# 1541-3d.net
KiCad netlist of a schematic drawn in EAGLE
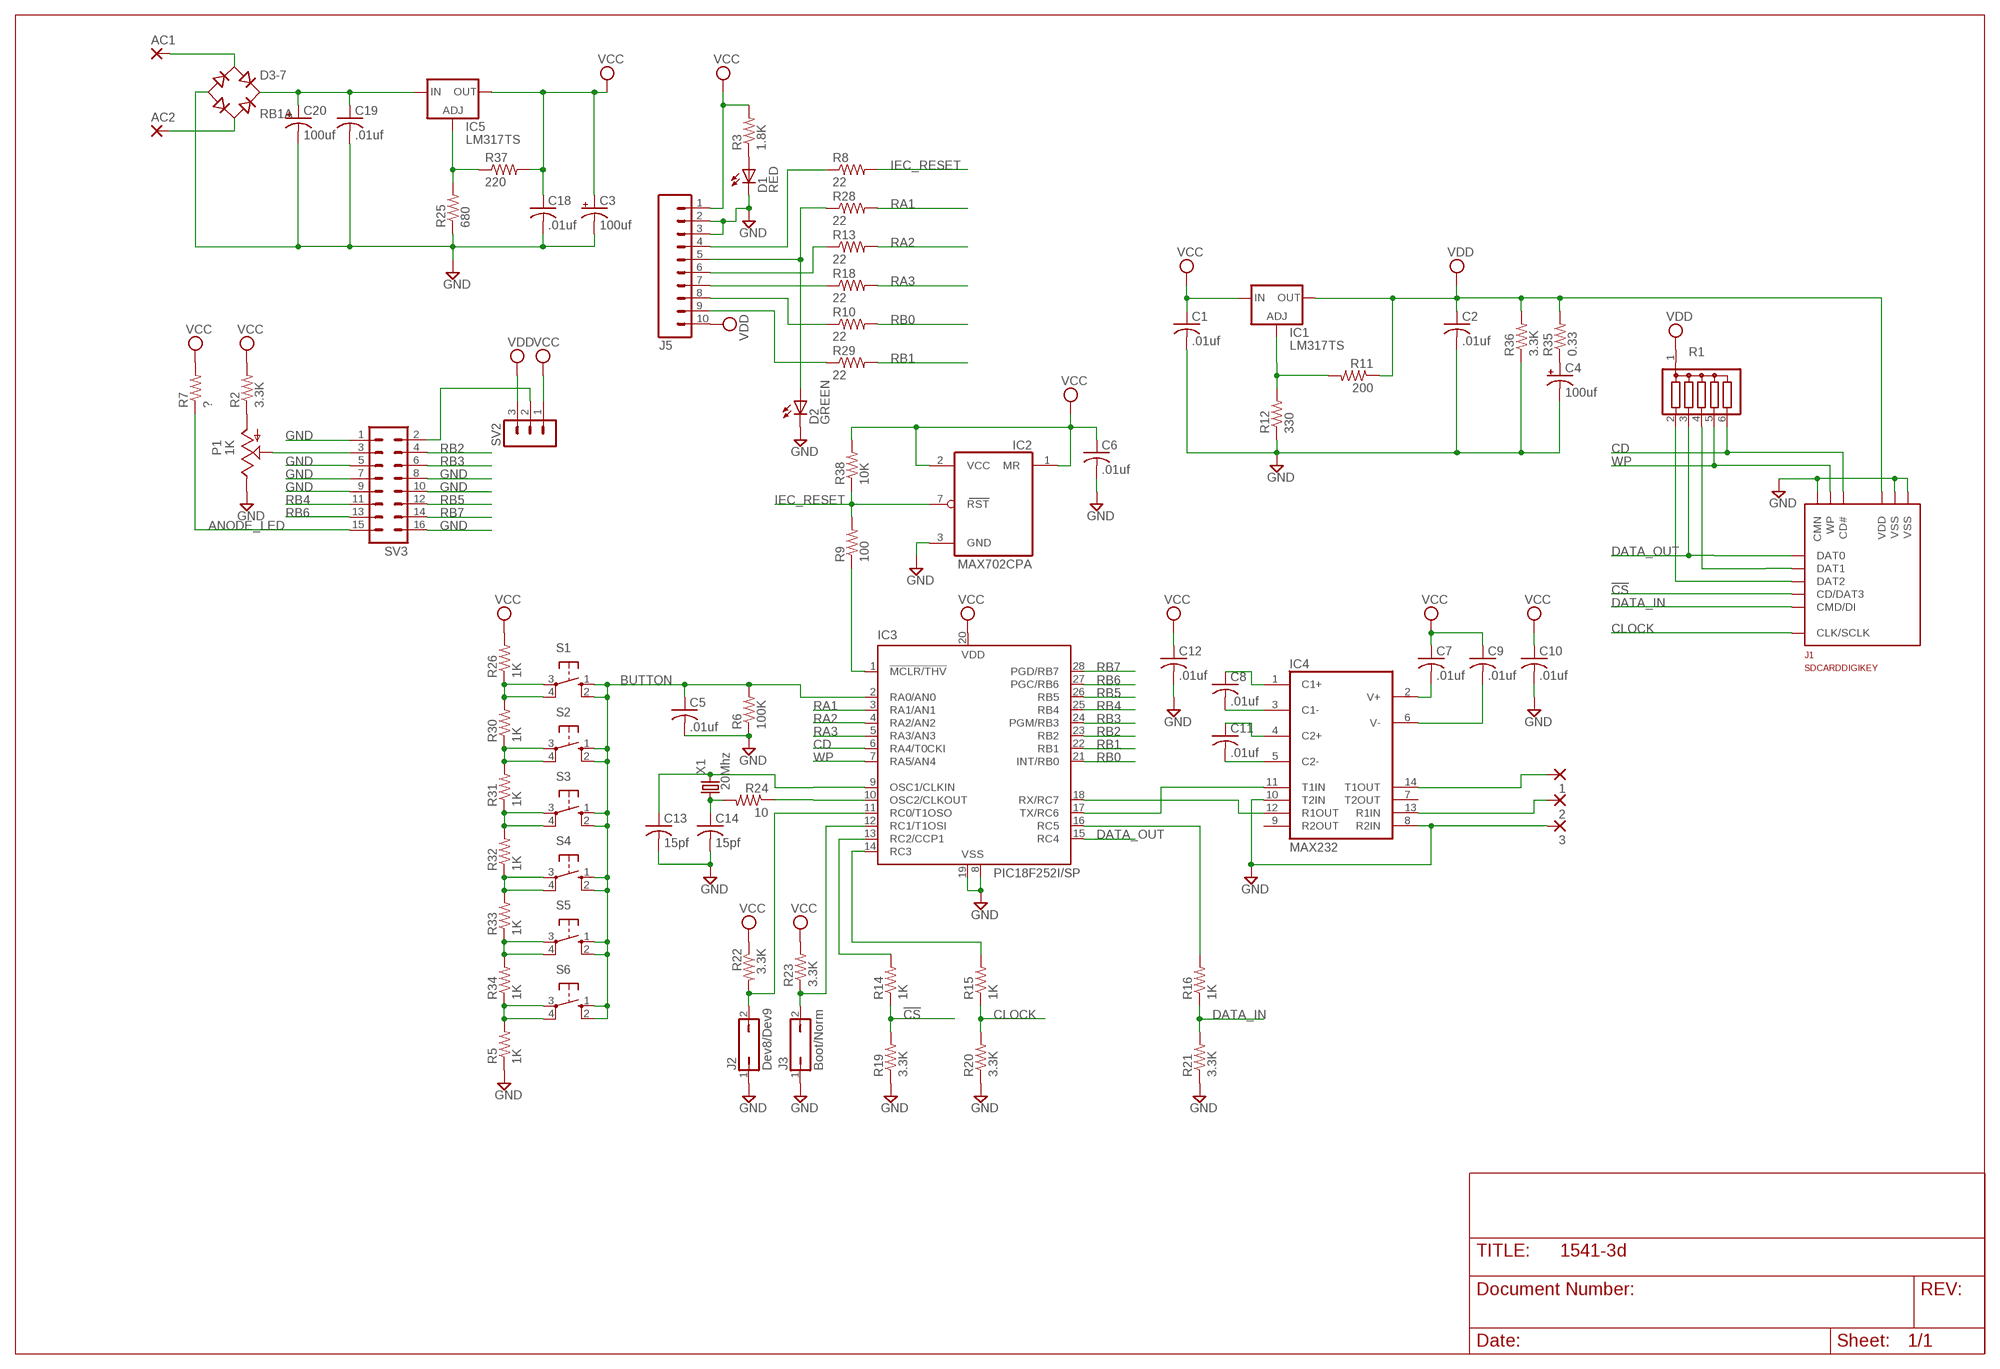
[diagram p0: schematic, sheet 1]

(export (version "E")
  (design (tool "Eeschema 10.0.6"))
  (components
    (comp (ref "1")
      (value "2,15/1,0")
      (footprint "eagle-import:2,15_1,0")
      (libsource (lib "eagle-import") (part "2,15/1,0"))
    )
    (comp (ref "2")
      (value "2,15/1,0")
      (footprint "eagle-import:2,15_1,0")
      (libsource (lib "eagle-import") (part "2,15/1,0"))
    )
    (comp (ref "3")
      (value "2,15/1,0")
      (footprint "eagle-import:2,15_1,0")
      (libsource (lib "eagle-import") (part "2,15/1,0"))
    )
    (comp (ref "AC1")
      (value "2,15/1,0")
      (footprint "eagle-import:2,15_1,0")
      (libsource (lib "eagle-import") (part "2,15/1,0"))
    )
    (comp (ref "AC2")
      (value "2,15/1,0")
      (footprint "eagle-import:2,15_1,0")
      (libsource (lib "eagle-import") (part "2,15/1,0"))
    )
    (comp (ref "C1")
      (value ".01uf")
      (footprint "eagle-import:C025-024X044")
      (libsource (lib "eagle-import") (part "C-US025-024X044"))
    )
    (comp (ref "C2")
      (value ".01uf")
      (footprint "eagle-import:C025-024X044")
      (libsource (lib "eagle-import") (part "C-US025-024X044"))
    )
    (comp (ref "C3")
      (value "100uf")
      (footprint "eagle-import:E2-5")
      (libsource (lib "eagle-import") (part "CPOL-USE2-5"))
    )
    (comp (ref "C4")
      (value "100uf")
      (footprint "eagle-import:E2-5")
      (libsource (lib "eagle-import") (part "CPOL-USE2-5"))
    )
    (comp (ref "C5")
      (value ".01uf")
      (footprint "eagle-import:C025-024X044")
      (libsource (lib "eagle-import") (part "C-US025-024X044"))
    )
    (comp (ref "C6")
      (value ".01uf")
      (footprint "eagle-import:C025-024X044")
      (libsource (lib "eagle-import") (part "C-US025-024X044"))
    )
    (comp (ref "C7")
      (value ".01uf")
      (footprint "eagle-import:C025-024X044")
      (libsource (lib "eagle-import") (part "C-US025-024X044"))
    )
    (comp (ref "C8")
      (value ".01uf")
      (footprint "eagle-import:C025-024X044")
      (libsource (lib "eagle-import") (part "C-US025-024X044"))
    )
    (comp (ref "C9")
      (value ".01uf")
      (footprint "eagle-import:C025-024X044")
      (libsource (lib "eagle-import") (part "C-US025-024X044"))
    )
    (comp (ref "C10")
      (value ".01uf")
      (footprint "eagle-import:C025-024X044")
      (libsource (lib "eagle-import") (part "C-US025-024X044"))
    )
    (comp (ref "C11")
      (value ".01uf")
      (footprint "eagle-import:C025-024X044")
      (libsource (lib "eagle-import") (part "C-US025-024X044"))
    )
    (comp (ref "C12")
      (value ".01uf")
      (footprint "eagle-import:C025-024X044")
      (libsource (lib "eagle-import") (part "C-US025-024X044"))
    )
    (comp (ref "C13")
      (value "15pf")
      (footprint "eagle-import:C025-024X044")
      (libsource (lib "eagle-import") (part "C-US025-024X044"))
    )
    (comp (ref "C14")
      (value "15pf")
      (footprint "eagle-import:C025-024X044")
      (libsource (lib "eagle-import") (part "C-US025-024X044"))
    )
    (comp (ref "C18")
      (value ".01uf")
      (footprint "eagle-import:C025-024X044")
      (libsource (lib "eagle-import") (part "C-US025-024X044"))
    )
    (comp (ref "C19")
      (value ".01uf")
      (footprint "eagle-import:C025-024X044")
      (libsource (lib "eagle-import") (part "C-US025-024X044"))
    )
    (comp (ref "C20")
      (value "100uf")
      (footprint "eagle-import:E2-5")
      (libsource (lib "eagle-import") (part "CPOL-USE2-5"))
    )
    (comp (ref "D1")
      (value "RED")
      (footprint "eagle-import:LED3MM")
      (libsource (lib "eagle-import") (part "LED3MM"))
    )
    (comp (ref "D2")
      (value "GREEN")
      (footprint "eagle-import:LED3MM")
      (libsource (lib "eagle-import") (part "LED3MM"))
    )
    (comp (ref "D3-7")
      (value "RB1A")
      (footprint "eagle-import:RB1A")
      (libsource (lib "eagle-import") (part "RB1A"))
    )
    (comp (ref "IC1")
      (value "LM317TS")
      (footprint "eagle-import:317TS")
      (libsource (lib "eagle-import") (part "LM317TS"))
    )
    (comp (ref "IC2")
      (value "MAX702CPA")
      (footprint "eagle-import:DIL08")
      (fields (field (name "MF") "MAXIM") (field (name "MPN") "MAX702CPA+"))
      (libsource (lib "eagle-import") (part "MAX702CPA"))
    )
    (comp (ref "IC3")
      (value "PIC18F252I/SP")
      (footprint "eagle-import:DIL28-3")
      (fields (field (name "MF") "MICROCHIP") (field (name "MPN") "PIC16F870-I/SP"))
      (libsource (lib "eagle-import") (part "PIC16870PF"))
    )
    (comp (ref "IC4")
      (value "MAX232")
      (footprint "eagle-import:DIL16")
      (fields (field (name "MF") "MAXIM") (field (name "MPN") "MAX232ACPE+"))
      (libsource (lib "eagle-import") (part "MAX232"))
    )
    (comp (ref "IC5")
      (value "LM317TS")
      (footprint "eagle-import:317TS")
      (libsource (lib "eagle-import") (part "LM317TS"))
    )
    (comp (ref "J1")
      (value "SDCARDDIGIKEY")
      (footprint "eagle-import:WM24032")
      (libsource (lib "eagle-import") (part "SDCARDDIGIKEY"))
    )
    (comp (ref "J2")
      (value "Dev8/Dev9")
      (footprint "eagle-import:JP1")
      (libsource (lib "eagle-import") (part "JP1Q"))
    )
    (comp (ref "J3")
      (value "Boot/Norm")
      (footprint "eagle-import:JP1")
      (libsource (lib "eagle-import") (part "JP1Q"))
    )
    (comp (ref "J5")
      (value "M10")
      (footprint "eagle-import:10P")
      (libsource (lib "eagle-import") (part "M10"))
    )
    (comp (ref "P1")
      (value "1K")
      (footprint "eagle-import:LI10")
      (libsource (lib "eagle-import") (part "TRIM_US-LI10"))
    )
    (comp (ref "R1")
      (value "G05R")
      (footprint "eagle-import:SIL6")
      (libsource (lib "eagle-import") (part "G05R"))
    )
    (comp (ref "R2")
      (value "3.3K")
      (footprint "eagle-import:0207_2V")
      (libsource (lib "eagle-import") (part "R-US_0207/2V"))
    )
    (comp (ref "R3")
      (value "1.8K")
      (footprint "eagle-import:0207_2V")
      (libsource (lib "eagle-import") (part "R-US_0207/2V"))
    )
    (comp (ref "R5")
      (value "1K")
      (footprint "eagle-import:0207_2V")
      (libsource (lib "eagle-import") (part "R-US_0207/2V"))
    )
    (comp (ref "R6")
      (value "100K")
      (footprint "eagle-import:0207_2V")
      (libsource (lib "eagle-import") (part "R-US_0207/2V"))
    )
    (comp (ref "R7")
      (value "?")
      (footprint "eagle-import:0207_2V")
      (libsource (lib "eagle-import") (part "R-US_0207/2V"))
    )
    (comp (ref "R8")
      (value "22")
      (footprint "eagle-import:0207_2V")
      (libsource (lib "eagle-import") (part "R-US_0207/2V"))
    )
    (comp (ref "R9")
      (value "100")
      (footprint "eagle-import:0207_2V")
      (libsource (lib "eagle-import") (part "R-US_0207/2V"))
    )
    (comp (ref "R10")
      (value "22")
      (footprint "eagle-import:0207_2V")
      (libsource (lib "eagle-import") (part "R-US_0207/2V"))
    )
    (comp (ref "R11")
      (value "200")
      (footprint "eagle-import:0207_2V")
      (libsource (lib "eagle-import") (part "R-US_0207/2V"))
    )
    (comp (ref "R12")
      (value "330")
      (footprint "eagle-import:0207_2V")
      (libsource (lib "eagle-import") (part "R-US_0207/2V"))
    )
    (comp (ref "R13")
      (value "22")
      (footprint "eagle-import:0207_2V")
      (libsource (lib "eagle-import") (part "R-US_0207/2V"))
    )
    (comp (ref "R14")
      (value "1K")
      (footprint "eagle-import:0207_2V")
      (libsource (lib "eagle-import") (part "R-US_0207/2V"))
    )
    (comp (ref "R15")
      (value "1K")
      (footprint "eagle-import:0207_2V")
      (libsource (lib "eagle-import") (part "R-US_0207/2V"))
    )
    (comp (ref "R16")
      (value "1K")
      (footprint "eagle-import:0207_2V")
      (libsource (lib "eagle-import") (part "R-US_0207/2V"))
    )
    (comp (ref "R18")
      (value "22")
      (footprint "eagle-import:0207_2V")
      (libsource (lib "eagle-import") (part "R-US_0207/2V"))
    )
    (comp (ref "R19")
      (value "3.3K")
      (footprint "eagle-import:0207_2V")
      (libsource (lib "eagle-import") (part "R-US_0207/2V"))
    )
    (comp (ref "R20")
      (value "3.3K")
      (footprint "eagle-import:0207_2V")
      (libsource (lib "eagle-import") (part "R-US_0207/2V"))
    )
    (comp (ref "R21")
      (value "3.3K")
      (footprint "eagle-import:0207_2V")
      (libsource (lib "eagle-import") (part "R-US_0207/2V"))
    )
    (comp (ref "R22")
      (value "3.3K")
      (footprint "eagle-import:0207_2V")
      (libsource (lib "eagle-import") (part "R-US_0207/2V"))
    )
    (comp (ref "R23")
      (value "3.3K")
      (footprint "eagle-import:0207_2V")
      (libsource (lib "eagle-import") (part "R-US_0207/2V"))
    )
    (comp (ref "R24")
      (value "10")
      (footprint "eagle-import:0207_2V")
      (libsource (lib "eagle-import") (part "R-US_0207/2V"))
    )
    (comp (ref "R25")
      (value "680")
      (footprint "eagle-import:0207_2V")
      (libsource (lib "eagle-import") (part "R-US_0207/2V"))
    )
    (comp (ref "R26")
      (value "1K")
      (footprint "eagle-import:0207_2V")
      (libsource (lib "eagle-import") (part "R-US_0207/2V"))
    )
    (comp (ref "R28")
      (value "22")
      (footprint "eagle-import:0207_2V")
      (libsource (lib "eagle-import") (part "R-US_0207/2V"))
    )
    (comp (ref "R29")
      (value "22")
      (footprint "eagle-import:0207_2V")
      (libsource (lib "eagle-import") (part "R-US_0207/2V"))
    )
    (comp (ref "R30")
      (value "1K")
      (footprint "eagle-import:0207_2V")
      (libsource (lib "eagle-import") (part "R-US_0207/2V"))
    )
    (comp (ref "R31")
      (value "1K")
      (footprint "eagle-import:0207_2V")
      (libsource (lib "eagle-import") (part "R-US_0207/2V"))
    )
    (comp (ref "R32")
      (value "1K")
      (footprint "eagle-import:0207_2V")
      (libsource (lib "eagle-import") (part "R-US_0207/2V"))
    )
    (comp (ref "R33")
      (value "1K")
      (footprint "eagle-import:0207_2V")
      (libsource (lib "eagle-import") (part "R-US_0207/2V"))
    )
    (comp (ref "R34")
      (value "1K")
      (footprint "eagle-import:0207_2V")
      (libsource (lib "eagle-import") (part "R-US_0207/2V"))
    )
    (comp (ref "R35")
      (value "0.33")
      (footprint "eagle-import:0207_2V")
      (libsource (lib "eagle-import") (part "R-US_0207/2V"))
    )
    (comp (ref "R36")
      (value "3.3K")
      (footprint "eagle-import:0207_2V")
      (libsource (lib "eagle-import") (part "R-US_0207/2V"))
    )
    (comp (ref "R37")
      (value "220")
      (footprint "eagle-import:0207_2V")
      (libsource (lib "eagle-import") (part "R-US_0207/2V"))
    )
    (comp (ref "R38")
      (value "10K")
      (footprint "eagle-import:0207_2V")
      (libsource (lib "eagle-import") (part "R-US_0207/2V"))
    )
    (comp (ref "S1")
      (value "10-XX")
      (footprint "eagle-import:B3F-10XX")
      (fields (field (name "MPN") "B3F-1000"))
      (libsource (lib "eagle-import") (part "10-XX"))
    )
    (comp (ref "S2")
      (value "10-XX")
      (footprint "eagle-import:B3F-10XX")
      (fields (field (name "MPN") "B3F-1000"))
      (libsource (lib "eagle-import") (part "10-XX"))
    )
    (comp (ref "S3")
      (value "10-XX")
      (footprint "eagle-import:B3F-10XX")
      (fields (field (name "MPN") "B3F-1000"))
      (libsource (lib "eagle-import") (part "10-XX"))
    )
    (comp (ref "S4")
      (value "10-XX")
      (footprint "eagle-import:B3F-10XX")
      (fields (field (name "MPN") "B3F-1000"))
      (libsource (lib "eagle-import") (part "10-XX"))
    )
    (comp (ref "S5")
      (value "10-XX")
      (footprint "eagle-import:B3F-10XX")
      (fields (field (name "MPN") "B3F-1000"))
      (libsource (lib "eagle-import") (part "10-XX"))
    )
    (comp (ref "S6")
      (value "10-XX")
      (footprint "eagle-import:B3F-10XX")
      (fields (field (name "MPN") "B3F-1000"))
      (libsource (lib "eagle-import") (part "10-XX"))
    )
    (comp (ref "SV2")
      (value "MA03-1")
      (footprint "eagle-import:MA03-1")
      (libsource (lib "eagle-import") (part "MA03-1"))
    )
    (comp (ref "SV3")
      (value "ML16")
      (footprint "eagle-import:ML16")
      (libsource (lib "eagle-import") (part "ML16"))
    )
    (comp (ref "X1")
      (value "20Mhz")
      (footprint "eagle-import:HC49U70")
      (libsource (lib "eagle-import") (part "CRYSTALHC49U70"))
    )
  )
  (nets
    (net (code "1") (name "/ANODE_LED") (class "Default")
      (node (ref "R7") (pin "1") (pinfunction "1_1") (pintype "passive"))
      (node (ref "SV3") (pin "15") (pinfunction "15_15") (pintype "passive"))
    )
    (net (code "2") (name "/BUTTON") (class "Default")
      (node (ref "C5") (pin "1") (pinfunction "1_1") (pintype "passive"))
      (node (ref "IC3") (pin "2") (pinfunction "RA0/AN0_2") (pintype "bidirectional"))
      (node (ref "R6") (pin "2") (pinfunction "2_2") (pintype "passive"))
      (node (ref "S1") (pin "1") (pinfunction "S_1") (pintype "passive"))
      (node (ref "S1") (pin "2") (pinfunction "S1_2") (pintype "passive"))
      (node (ref "S2") (pin "1") (pinfunction "S_1") (pintype "passive"))
      (node (ref "S2") (pin "2") (pinfunction "S1_2") (pintype "passive"))
      (node (ref "S3") (pin "1") (pinfunction "S_1") (pintype "passive"))
      (node (ref "S3") (pin "2") (pinfunction "S1_2") (pintype "passive"))
      (node (ref "S4") (pin "1") (pinfunction "S_1") (pintype "passive"))
      (node (ref "S4") (pin "2") (pinfunction "S1_2") (pintype "passive"))
      (node (ref "S5") (pin "1") (pinfunction "S_1") (pintype "passive"))
      (node (ref "S5") (pin "2") (pinfunction "S1_2") (pintype "passive"))
      (node (ref "S6") (pin "1") (pinfunction "S_1") (pintype "passive"))
      (node (ref "S6") (pin "2") (pinfunction "S1_2") (pintype "passive"))
    )
    (net (code "3") (name "/CD") (class "Default")
      (node (ref "IC3") (pin "6") (pinfunction "RA4/T0CKI_6") (pintype "bidirectional"))
      (node (ref "J1") (pin "CD") (pinfunction "CD#_CD") (pintype "output"))
      (node (ref "R1") (pin "6") (pinfunction "6_6") (pintype "passive"))
    )
    (net (code "4") (name "/CLOCK") (class "Default")
      (node (ref "J1") (pin "5") (pinfunction "CLK/SCLK_5") (pintype "bidirectional"))
      (node (ref "R15") (pin "1") (pinfunction "1_1") (pintype "passive"))
      (node (ref "R20") (pin "2") (pinfunction "2_2") (pintype "passive"))
    )
    (net (code "5") (name "/DATA_IN") (class "Default")
      (node (ref "J1") (pin "2") (pinfunction "CMD/DI_2") (pintype "bidirectional"))
      (node (ref "R16") (pin "1") (pinfunction "1_1") (pintype "passive"))
      (node (ref "R21") (pin "2") (pinfunction "2_2") (pintype "passive"))
    )
    (net (code "6") (name "/DATA_OUT") (class "Default")
      (node (ref "IC3") (pin "15") (pinfunction "RC4_15") (pintype "bidirectional"))
      (node (ref "J1") (pin "7") (pinfunction "DAT0_7") (pintype "bidirectional"))
      (node (ref "R1") (pin "3") (pinfunction "3_3") (pintype "passive"))
    )
    (net (code "7") (name "/IEC_RESET") (class "Default")
      (node (ref "IC2") (pin "7") (pinfunction "RST_7") (pintype "output"))
      (node (ref "R38") (pin "1") (pinfunction "1_1") (pintype "passive"))
      (node (ref "R8") (pin "2") (pinfunction "2_2") (pintype "passive"))
      (node (ref "R9") (pin "2") (pinfunction "2_2") (pintype "passive"))
    )
    (net (code "8") (name "/RA1") (class "Default")
      (node (ref "IC3") (pin "3") (pinfunction "RA1/AN1_3") (pintype "bidirectional"))
      (node (ref "R28") (pin "2") (pinfunction "2_2") (pintype "passive"))
    )
    (net (code "9") (name "/RA2") (class "Default")
      (node (ref "IC3") (pin "4") (pinfunction "RA2/AN2_4") (pintype "bidirectional"))
      (node (ref "R13") (pin "2") (pinfunction "2_2") (pintype "passive"))
    )
    (net (code "10") (name "/RA3") (class "Default")
      (node (ref "IC3") (pin "5") (pinfunction "RA3/AN3_5") (pintype "bidirectional"))
      (node (ref "R18") (pin "2") (pinfunction "2_2") (pintype "passive"))
    )
    (net (code "11") (name "/RB0") (class "Default")
      (node (ref "IC3") (pin "21") (pinfunction "INT/RB0_21") (pintype "bidirectional"))
      (node (ref "R10") (pin "2") (pinfunction "2_2") (pintype "passive"))
    )
    (net (code "12") (name "/RB1") (class "Default")
      (node (ref "IC3") (pin "22") (pinfunction "RB1_22") (pintype "bidirectional"))
      (node (ref "R29") (pin "2") (pinfunction "2_2") (pintype "passive"))
    )
    (net (code "13") (name "/RB2") (class "Default")
      (node (ref "IC3") (pin "23") (pinfunction "RB2_23") (pintype "bidirectional"))
      (node (ref "SV3") (pin "4") (pinfunction "4_4") (pintype "passive"))
    )
    (net (code "14") (name "/RB3") (class "Default")
      (node (ref "IC3") (pin "24") (pinfunction "PGM/RB3_24") (pintype "bidirectional"))
      (node (ref "SV3") (pin "6") (pinfunction "6_6") (pintype "passive"))
    )
    (net (code "15") (name "/RB4") (class "Default")
      (node (ref "IC3") (pin "25") (pinfunction "RB4_25") (pintype "bidirectional"))
      (node (ref "SV3") (pin "11") (pinfunction "11_11") (pintype "passive"))
    )
    (net (code "16") (name "/RB5") (class "Default")
      (node (ref "IC3") (pin "26") (pinfunction "RB5_26") (pintype "bidirectional"))
      (node (ref "SV3") (pin "12") (pinfunction "12_12") (pintype "passive"))
    )
    (net (code "17") (name "/RB6") (class "Default")
      (node (ref "IC3") (pin "27") (pinfunction "PGC/RB6_27") (pintype "bidirectional"))
      (node (ref "SV3") (pin "13") (pinfunction "13_13") (pintype "passive"))
    )
    (net (code "18") (name "/RB7") (class "Default")
      (node (ref "IC3") (pin "28") (pinfunction "PGD/RB7_28") (pintype "bidirectional"))
      (node (ref "SV3") (pin "14") (pinfunction "14_14") (pintype "passive"))
    )
    (net (code "19") (name "/WP") (class "Default")
      (node (ref "IC3") (pin "7") (pinfunction "RA5/AN4_7") (pintype "bidirectional"))
      (node (ref "J1") (pin "WP") (pinfunction "WP_WP") (pintype "output"))
      (node (ref "R1") (pin "5") (pinfunction "5_5") (pintype "passive"))
    )
    (net (code "20") (name "/~{CS}") (class "Default")
      (node (ref "J1") (pin "1") (pinfunction "CD/DAT3_1") (pintype "bidirectional"))
      (node (ref "R14") (pin "1") (pinfunction "1_1") (pintype "passive"))
      (node (ref "R19") (pin "2") (pinfunction "2_2") (pintype "passive"))
    )
    (net (code "21") (name "GND") (class "Default")
      (node (ref "3") (pin "1") (pinfunction "P_1") (pintype "passive"))
      (node (ref "C1") (pin "2") (pinfunction "2_2") (pintype "passive"))
      (node (ref "C10") (pin "2") (pinfunction "2_2") (pintype "passive"))
      (node (ref "C12") (pin "2") (pinfunction "2_2") (pintype "passive"))
      (node (ref "C13") (pin "2") (pinfunction "2_2") (pintype "passive"))
      (node (ref "C14") (pin "2") (pinfunction "2_2") (pintype "passive"))
      (node (ref "C18") (pin "2") (pinfunction "2_2") (pintype "passive"))
      (node (ref "C19") (pin "2") (pinfunction "2_2") (pintype "passive"))
      (node (ref "C2") (pin "2") (pinfunction "2_2") (pintype "passive"))
      (node (ref "C20") (pin "-") (pinfunction "-_-") (pintype "passive"))
      (node (ref "C3") (pin "-") (pinfunction "-_-") (pintype "passive"))
      (node (ref "C4") (pin "-") (pinfunction "-_-") (pintype "passive"))
      (node (ref "C5") (pin "2") (pinfunction "2_2") (pintype "passive"))
      (node (ref "C6") (pin "2") (pinfunction "2_2") (pintype "passive"))
      (node (ref "D1") (pin "K") (pinfunction "C_K") (pintype "passive"))
      (node (ref "D2") (pin "K") (pinfunction "C_K") (pintype "passive"))
      (node (ref "D3-7") (pin "-") (pinfunction "-_-") (pintype "passive"))
      (node (ref "IC2") (pin "3") (pinfunction "GND_3") (pintype "power_in"))
      (node (ref "IC3") (pin "19") (pinfunction "VSS_19") (pintype "power_in"))
      (node (ref "IC3") (pin "8") (pinfunction "VSS_8") (pintype "power_in"))
      (node (ref "IC4") (pin "10") (pinfunction "T2IN_10") (pintype "input"))
      (node (ref "IC4") (pin "8") (pinfunction "R2IN_8") (pintype "input"))
      (node (ref "J1") (pin "3") (pinfunction "VSS_3") (pintype "power_in"))
      (node (ref "J1") (pin "6") (pinfunction "VSS_6") (pintype "power_in"))
      (node (ref "J1") (pin "CMN") (pinfunction "CMN_CMN") (pintype "input"))
      (node (ref "J2") (pin "1") (pinfunction "1_1") (pintype "passive"))
      (node (ref "J3") (pin "1") (pinfunction "1_1") (pintype "passive"))
      (node (ref "J5") (pin "2") (pinfunction "2_2") (pintype "passive"))
      (node (ref "J5") (pin "3") (pinfunction "3_3") (pintype "passive"))
      (node (ref "P1") (pin "E") (pinfunction "E_E") (pintype "passive"))
      (node (ref "R12") (pin "1") (pinfunction "1_1") (pintype "passive"))
      (node (ref "R19") (pin "1") (pinfunction "1_1") (pintype "passive"))
      (node (ref "R20") (pin "1") (pinfunction "1_1") (pintype "passive"))
      (node (ref "R21") (pin "1") (pinfunction "1_1") (pintype "passive"))
      (node (ref "R25") (pin "1") (pinfunction "1_1") (pintype "passive"))
      (node (ref "R36") (pin "1") (pinfunction "1_1") (pintype "passive"))
      (node (ref "R5") (pin "1") (pinfunction "1_1") (pintype "passive"))
      (node (ref "R6") (pin "1") (pinfunction "1_1") (pintype "passive"))
      (node (ref "SV3") (pin "1") (pinfunction "1_1") (pintype "passive"))
      (node (ref "SV3") (pin "10") (pinfunction "10_10") (pintype "passive"))
      (node (ref "SV3") (pin "16") (pinfunction "16_16") (pintype "passive"))
      (node (ref "SV3") (pin "5") (pinfunction "5_5") (pintype "passive"))
      (node (ref "SV3") (pin "7") (pinfunction "7_7") (pintype "passive"))
      (node (ref "SV3") (pin "8") (pinfunction "8_8") (pintype "passive"))
      (node (ref "SV3") (pin "9") (pinfunction "9_9") (pintype "passive"))
    )
    (net (code "22") (name "Net-(1-P)") (class "Default")
      (node (ref "1") (pin "1") (pinfunction "P_1") (pintype "passive"))
      (node (ref "IC4") (pin "14") (pinfunction "T1OUT_14") (pintype "output"))
    )
    (net (code "23") (name "Net-(2-P)") (class "Default")
      (node (ref "2") (pin "1") (pinfunction "P_1") (pintype "passive"))
      (node (ref "IC4") (pin "13") (pinfunction "R1IN_13") (pintype "input"))
    )
    (net (code "24") (name "Net-(AC1-P)") (class "Default")
      (node (ref "AC1") (pin "1") (pinfunction "P_1") (pintype "passive"))
      (node (ref "D3-7") (pin "AC1") (pinfunction "AC1_AC1") (pintype "passive"))
    )
    (net (code "25") (name "Net-(AC2-P)") (class "Default")
      (node (ref "AC2") (pin "1") (pinfunction "P_1") (pintype "passive"))
      (node (ref "D3-7") (pin "AC2") (pinfunction "AC2_AC2") (pintype "passive"))
    )
    (net (code "26") (name "Net-(C4-Pad+)") (class "Default")
      (node (ref "C4") (pin "+") (pinfunction "+_+") (pintype "passive"))
      (node (ref "R35") (pin "1") (pinfunction "1_1") (pintype "passive"))
    )
    (net (code "27") (name "Net-(C14-Pad1)") (class "Default")
      (node (ref "C14") (pin "1") (pinfunction "1_1") (pintype "passive"))
      (node (ref "R24") (pin "2") (pinfunction "2_2") (pintype "passive"))
      (node (ref "X1") (pin "1") (pinfunction "1_1") (pintype "passive"))
    )
    (net (code "28") (name "Net-(D1-PadA)") (class "Default")
      (node (ref "D1") (pin "A") (pinfunction "A_A") (pintype "passive"))
      (node (ref "R3") (pin "1") (pinfunction "1_1") (pintype "passive"))
    )
    (net (code "29") (name "Net-(D2-PadA)") (class "Default")
      (node (ref "D2") (pin "A") (pinfunction "A_A") (pintype "passive"))
      (node (ref "J5") (pin "5") (pinfunction "5_5") (pintype "passive"))
      (node (ref "R28") (pin "1") (pinfunction "1_1") (pintype "passive"))
    )
    (net (code "30") (name "Net-(IC1-ADJ)") (class "Default")
      (node (ref "IC1") (pin "1") (pinfunction "ADJ_1") (pintype "input"))
      (node (ref "R11") (pin "2") (pinfunction "2_2") (pintype "passive"))
      (node (ref "R12") (pin "2") (pinfunction "2_2") (pintype "passive"))
    )
    (net (code "31") (name "Net-(IC3-OSC1{slash}CLKIN)") (class "Default")
      (node (ref "C13") (pin "1") (pinfunction "1_1") (pintype "passive"))
      (node (ref "IC3") (pin "9") (pinfunction "OSC1/CLKIN_9") (pintype "input"))
      (node (ref "X1") (pin "2") (pinfunction "2_2") (pintype "passive"))
    )
    (net (code "32") (name "Net-(IC3-OSC2{slash}CLKOUT)") (class "Default")
      (node (ref "IC3") (pin "10") (pinfunction "OSC2/CLKOUT_10") (pintype "output"))
      (node (ref "R24") (pin "1") (pinfunction "1_1") (pintype "passive"))
    )
    (net (code "33") (name "Net-(IC3-RC0{slash}T1OSO)") (class "Default")
      (node (ref "IC3") (pin "11") (pinfunction "RC0/T1OSO_11") (pintype "bidirectional"))
      (node (ref "J2") (pin "2") (pinfunction "2_2") (pintype "passive"))
      (node (ref "R22") (pin "2") (pinfunction "2_2") (pintype "passive"))
    )
    (net (code "34") (name "Net-(IC3-RC1{slash}T1OSI)") (class "Default")
      (node (ref "IC3") (pin "12") (pinfunction "RC1/T1OSI_12") (pintype "bidirectional"))
      (node (ref "J3") (pin "2") (pinfunction "2_2") (pintype "passive"))
      (node (ref "R23") (pin "1") (pinfunction "1_1") (pintype "passive"))
    )
    (net (code "35") (name "Net-(IC3-RC2{slash}CCP1)") (class "Default")
      (node (ref "IC3") (pin "13") (pinfunction "RC2/CCP1_13") (pintype "bidirectional"))
      (node (ref "R14") (pin "2") (pinfunction "2_2") (pintype "passive"))
    )
    (net (code "36") (name "Net-(IC3-RC3)") (class "Default")
      (node (ref "IC3") (pin "14") (pinfunction "RC3_14") (pintype "bidirectional"))
      (node (ref "R15") (pin "2") (pinfunction "2_2") (pintype "passive"))
    )
    (net (code "37") (name "Net-(IC3-RC5)") (class "Default")
      (node (ref "IC3") (pin "16") (pinfunction "RC5_16") (pintype "bidirectional"))
      (node (ref "R16") (pin "2") (pinfunction "2_2") (pintype "passive"))
    )
    (net (code "38") (name "Net-(IC3-RX{slash}RC7)") (class "Default")
      (node (ref "IC3") (pin "18") (pinfunction "RX/RC7_18") (pintype "bidirectional"))
      (node (ref "IC4") (pin "12") (pinfunction "R1OUT_12") (pintype "output"))
    )
    (net (code "39") (name "Net-(IC3-TX{slash}RC6)") (class "Default")
      (node (ref "IC3") (pin "17") (pinfunction "TX/RC6_17") (pintype "bidirectional"))
      (node (ref "IC4") (pin "11") (pinfunction "T1IN_11") (pintype "input"))
    )
    (net (code "40") (name "Net-(IC3-~{MCLR{slash}THV})") (class "Default")
      (node (ref "IC3") (pin "1") (pinfunction "~{MCLR/THV}_1") (pintype "input"))
      (node (ref "R9") (pin "1") (pinfunction "1_1") (pintype "passive"))
    )
    (net (code "41") (name "Net-(IC4A-C1+)") (class "Default")
      (node (ref "C8") (pin "1") (pinfunction "1_1") (pintype "passive"))
      (node (ref "IC4") (pin "1") (pinfunction "C1+_1") (pintype "bidirectional"))
    )
    (net (code "42") (name "Net-(IC4A-C1-)") (class "Default")
      (node (ref "C8") (pin "2") (pinfunction "2_2") (pintype "passive"))
      (node (ref "IC4") (pin "3") (pinfunction "C1-_3") (pintype "bidirectional"))
    )
    (net (code "43") (name "Net-(IC4A-C2+)") (class "Default")
      (node (ref "C11") (pin "1") (pinfunction "1_1") (pintype "passive"))
      (node (ref "IC4") (pin "4") (pinfunction "C2+_4") (pintype "bidirectional"))
    )
    (net (code "44") (name "Net-(IC4A-C2-)") (class "Default")
      (node (ref "C11") (pin "2") (pinfunction "2_2") (pintype "passive"))
      (node (ref "IC4") (pin "5") (pinfunction "C2-_5") (pintype "bidirectional"))
    )
    (net (code "45") (name "Net-(IC4A-V+)") (class "Default")
      (node (ref "C7") (pin "2") (pinfunction "2_2") (pintype "passive"))
      (node (ref "IC4") (pin "2") (pinfunction "V+_2") (pintype "bidirectional"))
    )
    (net (code "46") (name "Net-(IC4A-V-)") (class "Default")
      (node (ref "C9") (pin "2") (pinfunction "2_2") (pintype "passive"))
      (node (ref "IC4") (pin "6") (pinfunction "V-_6") (pintype "bidirectional"))
    )
    (net (code "47") (name "Net-(IC5-ADJ)") (class "Default")
      (node (ref "IC5") (pin "1") (pinfunction "ADJ_1") (pintype "input"))
      (node (ref "R25") (pin "2") (pinfunction "2_2") (pintype "passive"))
      (node (ref "R37") (pin "1") (pinfunction "1_1") (pintype "passive"))
    )
    (net (code "48") (name "Net-(IC5-IN)") (class "Default")
      (node (ref "C19") (pin "1") (pinfunction "1_1") (pintype "passive"))
      (node (ref "C20") (pin "+") (pinfunction "+_+") (pintype "passive"))
      (node (ref "D3-7") (pin "+") (pinfunction "+_+") (pintype "passive"))
      (node (ref "IC5") (pin "3") (pinfunction "IN_3") (pintype "input"))
    )
    (net (code "49") (name "Net-(J1A-DAT1)") (class "Default")
      (node (ref "J1") (pin "8") (pinfunction "DAT1_8") (pintype "bidirectional"))
      (node (ref "R1") (pin "4") (pinfunction "4_4") (pintype "passive"))
    )
    (net (code "50") (name "Net-(J1A-DAT2)") (class "Default")
      (node (ref "J1") (pin "9") (pinfunction "DAT2_9") (pintype "bidirectional"))
      (node (ref "R1") (pin "2") (pinfunction "2_2") (pintype "passive"))
    )
    (net (code "51") (name "Net-(J5-Pad4)") (class "Default")
      (node (ref "J5") (pin "4") (pinfunction "4_4") (pintype "passive"))
      (node (ref "R8") (pin "1") (pinfunction "1_1") (pintype "passive"))
    )
    (net (code "52") (name "Net-(J5-Pad6)") (class "Default")
      (node (ref "J5") (pin "6") (pinfunction "6_6") (pintype "passive"))
      (node (ref "R13") (pin "1") (pinfunction "1_1") (pintype "passive"))
    )
    (net (code "53") (name "Net-(J5-Pad7)") (class "Default")
      (node (ref "J5") (pin "7") (pinfunction "7_7") (pintype "passive"))
      (node (ref "R18") (pin "1") (pinfunction "1_1") (pintype "passive"))
    )
    (net (code "54") (name "Net-(J5-Pad8)") (class "Default")
      (node (ref "J5") (pin "8") (pinfunction "8_8") (pintype "passive"))
      (node (ref "R10") (pin "1") (pinfunction "1_1") (pintype "passive"))
    )
    (net (code "55") (name "Net-(J5-Pad9)") (class "Default")
      (node (ref "J5") (pin "9") (pinfunction "9_9") (pintype "passive"))
      (node (ref "R29") (pin "1") (pinfunction "1_1") (pintype "passive"))
    )
    (net (code "56") (name "Net-(P1-PadA)") (class "Default")
      (node (ref "P1") (pin "A") (pinfunction "A_A") (pintype "passive"))
      (node (ref "R2") (pin "1") (pinfunction "1_1") (pintype "passive"))
    )
    (net (code "57") (name "Net-(P1-PadS)") (class "Default")
      (node (ref "P1") (pin "S") (pinfunction "S_S") (pintype "passive"))
      (node (ref "SV3") (pin "3") (pinfunction "3_3") (pintype "passive"))
    )
    (net (code "58") (name "Net-(S1-P)") (class "Default")
      (node (ref "R26") (pin "1") (pinfunction "1_1") (pintype "passive"))
      (node (ref "R30") (pin "2") (pinfunction "2_2") (pintype "passive"))
      (node (ref "S1") (pin "3") (pinfunction "P_3") (pintype "passive"))
      (node (ref "S1") (pin "4") (pinfunction "P1_4") (pintype "passive"))
    )
    (net (code "59") (name "Net-(S2-P)") (class "Default")
      (node (ref "R30") (pin "1") (pinfunction "1_1") (pintype "passive"))
      (node (ref "R31") (pin "2") (pinfunction "2_2") (pintype "passive"))
      (node (ref "S2") (pin "3") (pinfunction "P_3") (pintype "passive"))
      (node (ref "S2") (pin "4") (pinfunction "P1_4") (pintype "passive"))
    )
    (net (code "60") (name "Net-(S3-P)") (class "Default")
      (node (ref "R31") (pin "1") (pinfunction "1_1") (pintype "passive"))
      (node (ref "R32") (pin "2") (pinfunction "2_2") (pintype "passive"))
      (node (ref "S3") (pin "3") (pinfunction "P_3") (pintype "passive"))
      (node (ref "S3") (pin "4") (pinfunction "P1_4") (pintype "passive"))
    )
    (net (code "61") (name "Net-(S4-P)") (class "Default")
      (node (ref "R32") (pin "1") (pinfunction "1_1") (pintype "passive"))
      (node (ref "R33") (pin "2") (pinfunction "2_2") (pintype "passive"))
      (node (ref "S4") (pin "3") (pinfunction "P_3") (pintype "passive"))
      (node (ref "S4") (pin "4") (pinfunction "P1_4") (pintype "passive"))
    )
    (net (code "62") (name "Net-(S5-P)") (class "Default")
      (node (ref "R33") (pin "1") (pinfunction "1_1") (pintype "passive"))
      (node (ref "R34") (pin "2") (pinfunction "2_2") (pintype "passive"))
      (node (ref "S5") (pin "3") (pinfunction "P_3") (pintype "passive"))
      (node (ref "S5") (pin "4") (pinfunction "P1_4") (pintype "passive"))
    )
    (net (code "63") (name "Net-(S6-P)") (class "Default")
      (node (ref "R34") (pin "1") (pinfunction "1_1") (pintype "passive"))
      (node (ref "R5") (pin "2") (pinfunction "2_2") (pintype "passive"))
      (node (ref "S6") (pin "3") (pinfunction "P_3") (pintype "passive"))
      (node (ref "S6") (pin "4") (pinfunction "P1_4") (pintype "passive"))
    )
    (net (code "64") (name "Net-(SV2-Pad2)") (class "Default")
      (node (ref "SV2") (pin "2") (pinfunction "2_2") (pintype "passive"))
      (node (ref "SV3") (pin "2") (pinfunction "2_2") (pintype "passive"))
    )
    (net (code "65") (name "VCC") (class "Default")
      (node (ref "C1") (pin "1") (pinfunction "1_1") (pintype "passive"))
      (node (ref "C10") (pin "1") (pinfunction "1_1") (pintype "passive"))
      (node (ref "C12") (pin "1") (pinfunction "1_1") (pintype "passive"))
      (node (ref "C18") (pin "1") (pinfunction "1_1") (pintype "passive"))
      (node (ref "C3") (pin "+") (pinfunction "+_+") (pintype "passive"))
      (node (ref "C6") (pin "1") (pinfunction "1_1") (pintype "passive"))
      (node (ref "C7") (pin "1") (pinfunction "1_1") (pintype "passive"))
      (node (ref "C9") (pin "1") (pinfunction "1_1") (pintype "passive"))
      (node (ref "IC1") (pin "3") (pinfunction "IN_3") (pintype "input"))
      (node (ref "IC2") (pin "1") (pinfunction "MR_1") (pintype "input"))
      (node (ref "IC2") (pin "2") (pinfunction "VCC_2") (pintype "power_in"))
      (node (ref "IC3") (pin "20") (pinfunction "VDD_20") (pintype "power_in"))
      (node (ref "IC5") (pin "2") (pinfunction "OUT_2") (pintype "passive"))
      (node (ref "J5") (pin "1") (pinfunction "1_1") (pintype "passive"))
      (node (ref "R2") (pin "2") (pinfunction "2_2") (pintype "passive"))
      (node (ref "R22") (pin "1") (pinfunction "1_1") (pintype "passive"))
      (node (ref "R23") (pin "2") (pinfunction "2_2") (pintype "passive"))
      (node (ref "R26") (pin "2") (pinfunction "2_2") (pintype "passive"))
      (node (ref "R3") (pin "2") (pinfunction "2_2") (pintype "passive"))
      (node (ref "R37") (pin "2") (pinfunction "2_2") (pintype "passive"))
      (node (ref "R38") (pin "2") (pinfunction "2_2") (pintype "passive"))
      (node (ref "R7") (pin "2") (pinfunction "2_2") (pintype "passive"))
      (node (ref "SV2") (pin "1") (pinfunction "1_1") (pintype "passive"))
    )
    (net (code "66") (name "VDD") (class "Default")
      (node (ref "C2") (pin "1") (pinfunction "1_1") (pintype "passive"))
      (node (ref "IC1") (pin "2") (pinfunction "OUT_2") (pintype "passive"))
      (node (ref "J1") (pin "4") (pinfunction "VDD_4") (pintype "power_in"))
      (node (ref "J5") (pin "10") (pinfunction "10_10") (pintype "passive"))
      (node (ref "R1") (pin "1") (pinfunction "1_1") (pintype "passive"))
      (node (ref "R11") (pin "1") (pinfunction "1_1") (pintype "passive"))
      (node (ref "R35") (pin "2") (pinfunction "2_2") (pintype "passive"))
      (node (ref "R36") (pin "2") (pinfunction "2_2") (pintype "passive"))
      (node (ref "SV2") (pin "3") (pinfunction "3_3") (pintype "passive"))
    )
    (net (code "67") (name "unconnected-(IC4A-R2OUT-Pad9)") (class "Default")
      (node (ref "IC4") (pin "9") (pinfunction "R2OUT_9") (pintype "output"))
    )
    (net (code "68") (name "unconnected-(IC4A-T2OUT-Pad7)") (class "Default")
      (node (ref "IC4") (pin "7") (pinfunction "T2OUT_7") (pintype "output"))
    )
  )
)
